# wisleep_dbg.net
KiCad netlist of a schematic drawn in EAGLE
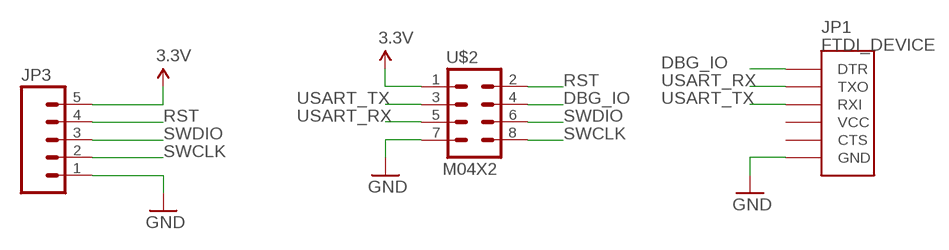
[diagram p0: schematic, sheet 1]

(export (version "E")
  (design (tool "Eeschema 10.0.6"))
  (components
    (comp (ref "JP1")
      (value "FTDI_DEVICE")
      (footprint "eagle-import:FTDI_DEVICE_SIDE")
      (libsource (lib "eagle-import") (part "FTDI_DEVICE"))
    )
    (comp (ref "JP3")
      (value "M05LOCK")
      (footprint "eagle-import:1X05_LOCK")
      (libsource (lib "eagle-import") (part "M05LOCK"))
    )
    (comp (ref "U$2")
      (value "M04X2")
      (footprint "eagle-import:2X4")
      (libsource (lib "eagle-import") (part "M04X2"))
    )
  )
  (nets
    (net (code "1") (name "/DBG_IO") (class "Default")
      (node (ref "JP1") (pin "P$1") (pinfunction "DTR_P$1") (pintype "bidirectional"))
      (node (ref "U$2") (pin "4") (pinfunction "4_4") (pintype "passive"))
    )
    (net (code "2") (name "/RST") (class "Default")
      (node (ref "JP3") (pin "4") (pinfunction "4_4") (pintype "passive"))
      (node (ref "U$2") (pin "2") (pinfunction "2_2") (pintype "passive"))
    )
    (net (code "3") (name "/SWCLK") (class "Default")
      (node (ref "JP3") (pin "2") (pinfunction "2_2") (pintype "passive"))
      (node (ref "U$2") (pin "8") (pinfunction "8_8") (pintype "passive"))
    )
    (net (code "4") (name "/SWDIO") (class "Default")
      (node (ref "JP3") (pin "3") (pinfunction "3_3") (pintype "passive"))
      (node (ref "U$2") (pin "6") (pinfunction "6_6") (pintype "passive"))
    )
    (net (code "5") (name "/USART_RX") (class "Default")
      (node (ref "JP1") (pin "P$2") (pinfunction "TXO_P$2") (pintype "bidirectional"))
      (node (ref "U$2") (pin "5") (pinfunction "5_5") (pintype "passive"))
    )
    (net (code "6") (name "/USART_TX") (class "Default")
      (node (ref "JP1") (pin "P$3") (pinfunction "RXI_P$3") (pintype "bidirectional"))
      (node (ref "U$2") (pin "3") (pinfunction "3_3") (pintype "passive"))
    )
    (net (code "7") (name "3.3V") (class "Default")
      (node (ref "JP3") (pin "5") (pinfunction "5_5") (pintype "passive"))
      (node (ref "U$2") (pin "1") (pinfunction "1_1") (pintype "passive"))
    )
    (net (code "8") (name "GND") (class "Default")
      (node (ref "JP1") (pin "P$6") (pinfunction "GND_P$6") (pintype "bidirectional"))
      (node (ref "JP3") (pin "1") (pinfunction "1_1") (pintype "passive"))
      (node (ref "U$2") (pin "7") (pinfunction "7_7") (pintype "passive"))
    )
    (net (code "9") (name "unconnected-(JP1-CTS-PadP$5)") (class "Default")
      (node (ref "JP1") (pin "P$5") (pinfunction "CTS_P$5") (pintype "bidirectional"))
    )
    (net (code "10") (name "unconnected-(JP1-VCC-PadP$4)") (class "Default")
      (node (ref "JP1") (pin "P$4") (pinfunction "VCC_P$4") (pintype "bidirectional"))
    )
  )
)
